# KLogShield_Interface_Rev1.net
KiCad netlist of a schematic drawn in Altium Designer
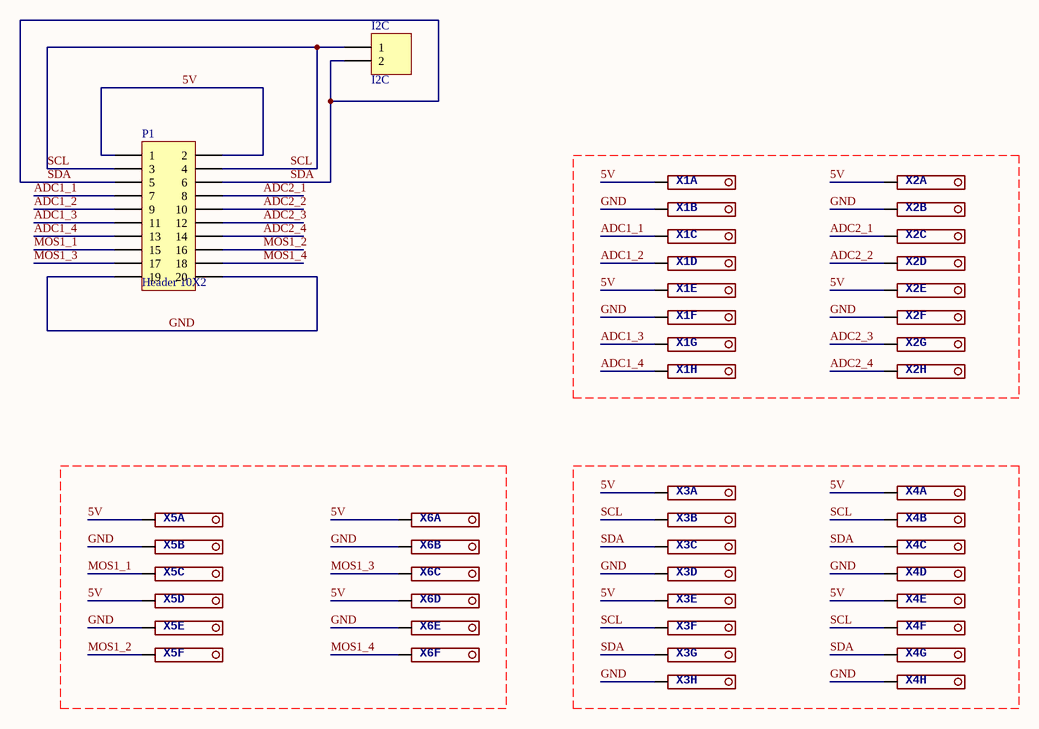
[diagram p0: KLogShield_Interface_Rev1.SchDoc]

(export (version "E")
  (design (tool "Eeschema 10.0.6"))
  (components
    (comp (ref "I2C")
      (value "I2C")
      (footprint "HDR1X2")
      (description "Header, 2-Pin")
      (fields (field (name "PUBLISHER") "Altium Limited"))
      (libsource (lib "Miscellaneous Connectors") (part "Header 2"))
    )
    (comp (ref "P1")
      (value "Header 10X2")
      (footprint "HDR2X10")
      (description "Header, 10-Pin, Dual row")
      (fields (field (name "PUBLISHER") "Altium Limited"))
      (libsource (lib "Miscellaneous Connectors") (part "Header 10X2"))
    )
    (comp (ref "X1") (value "~") (footprint "1751303") (libsource (lib "con-phoenix-350") (part "1751303")))
    (comp (ref "X2") (value "~") (footprint "1751303") (libsource (lib "con-phoenix-350") (part "1751303")))
    (comp (ref "X3") (value "~") (footprint "1751303") (libsource (lib "con-phoenix-350") (part "1751303")))
    (comp (ref "X4") (value "~") (footprint "1751303") (libsource (lib "con-phoenix-350") (part "1751303")))
    (comp (ref "X5")
      (value "~")
      (footprint "1751280")
      (fields (field (name "MPN") "1751280"))
      (libsource (lib "con-phoenix-350") (part "1751280"))
    )
    (comp (ref "X6")
      (value "~")
      (footprint "1751280")
      (fields (field (name "MPN") "1751280"))
      (libsource (lib "con-phoenix-350") (part "1751280"))
    )
  )
  (nets
    (net (code "1") (name "/5V") (class "Default")
      (node (ref "P1") (pin "1") (pinfunction "1_1") (pintype "passive"))
      (node (ref "P1") (pin "2") (pinfunction "2_2") (pintype "passive"))
      (node (ref "X1") (pin "1") (pinfunction "K_1") (pintype "passive"))
      (node (ref "X1") (pin "5") (pinfunction "K_5") (pintype "passive"))
      (node (ref "X2") (pin "1") (pinfunction "K_1") (pintype "passive"))
      (node (ref "X2") (pin "5") (pinfunction "K_5") (pintype "passive"))
      (node (ref "X3") (pin "1") (pinfunction "K_1") (pintype "passive"))
      (node (ref "X3") (pin "5") (pinfunction "K_5") (pintype "passive"))
      (node (ref "X4") (pin "1") (pinfunction "K_1") (pintype "passive"))
      (node (ref "X4") (pin "5") (pinfunction "K_5") (pintype "passive"))
      (node (ref "X5") (pin "1") (pinfunction "K_1") (pintype "passive"))
      (node (ref "X5") (pin "4") (pinfunction "K_4") (pintype "passive"))
      (node (ref "X6") (pin "1") (pinfunction "K_1") (pintype "passive"))
      (node (ref "X6") (pin "4") (pinfunction "K_4") (pintype "passive"))
    )
    (net (code "2") (name "/ADC1_1") (class "Default")
      (node (ref "P1") (pin "7") (pinfunction "7_7") (pintype "passive"))
      (node (ref "X1") (pin "3") (pinfunction "K_3") (pintype "passive"))
    )
    (net (code "3") (name "/ADC1_2") (class "Default")
      (node (ref "P1") (pin "9") (pinfunction "9_9") (pintype "passive"))
      (node (ref "X1") (pin "4") (pinfunction "K_4") (pintype "passive"))
    )
    (net (code "4") (name "/ADC1_3") (class "Default")
      (node (ref "P1") (pin "11") (pinfunction "11_11") (pintype "passive"))
      (node (ref "X1") (pin "7") (pinfunction "K_7") (pintype "passive"))
    )
    (net (code "5") (name "/ADC1_4") (class "Default")
      (node (ref "P1") (pin "13") (pinfunction "13_13") (pintype "passive"))
      (node (ref "X1") (pin "8") (pinfunction "K_8") (pintype "passive"))
    )
    (net (code "6") (name "/ADC2_1") (class "Default")
      (node (ref "P1") (pin "8") (pinfunction "8_8") (pintype "passive"))
      (node (ref "X2") (pin "3") (pinfunction "K_3") (pintype "passive"))
    )
    (net (code "7") (name "/ADC2_2") (class "Default")
      (node (ref "P1") (pin "10") (pinfunction "10_10") (pintype "passive"))
      (node (ref "X2") (pin "4") (pinfunction "K_4") (pintype "passive"))
    )
    (net (code "8") (name "/ADC2_3") (class "Default")
      (node (ref "P1") (pin "12") (pinfunction "12_12") (pintype "passive"))
      (node (ref "X2") (pin "7") (pinfunction "K_7") (pintype "passive"))
    )
    (net (code "9") (name "/ADC2_4") (class "Default")
      (node (ref "P1") (pin "14") (pinfunction "14_14") (pintype "passive"))
      (node (ref "X2") (pin "8") (pinfunction "K_8") (pintype "passive"))
    )
    (net (code "10") (name "/GND") (class "Default")
      (node (ref "P1") (pin "19") (pinfunction "19_19") (pintype "passive"))
      (node (ref "P1") (pin "20") (pinfunction "20_20") (pintype "passive"))
      (node (ref "X1") (pin "2") (pinfunction "K_2") (pintype "passive"))
      (node (ref "X1") (pin "6") (pinfunction "K_6") (pintype "passive"))
      (node (ref "X2") (pin "2") (pinfunction "K_2") (pintype "passive"))
      (node (ref "X2") (pin "6") (pinfunction "K_6") (pintype "passive"))
      (node (ref "X3") (pin "4") (pinfunction "K_4") (pintype "passive"))
      (node (ref "X3") (pin "8") (pinfunction "K_8") (pintype "passive"))
      (node (ref "X4") (pin "4") (pinfunction "K_4") (pintype "passive"))
      (node (ref "X4") (pin "8") (pinfunction "K_8") (pintype "passive"))
      (node (ref "X5") (pin "2") (pinfunction "K_2") (pintype "passive"))
      (node (ref "X5") (pin "5") (pinfunction "K_5") (pintype "passive"))
      (node (ref "X6") (pin "2") (pinfunction "K_2") (pintype "passive"))
      (node (ref "X6") (pin "5") (pinfunction "K_5") (pintype "passive"))
    )
    (net (code "11") (name "/MOS1_1") (class "Default")
      (node (ref "P1") (pin "15") (pinfunction "15_15") (pintype "passive"))
      (node (ref "X5") (pin "3") (pinfunction "K_3") (pintype "passive"))
    )
    (net (code "12") (name "/MOS1_2") (class "Default")
      (node (ref "P1") (pin "16") (pinfunction "16_16") (pintype "passive"))
      (node (ref "X5") (pin "6") (pinfunction "K_6") (pintype "passive"))
    )
    (net (code "13") (name "/MOS1_3") (class "Default")
      (node (ref "P1") (pin "17") (pinfunction "17_17") (pintype "passive"))
      (node (ref "X6") (pin "3") (pinfunction "K_3") (pintype "passive"))
    )
    (net (code "14") (name "/MOS1_4") (class "Default")
      (node (ref "P1") (pin "18") (pinfunction "18_18") (pintype "passive"))
      (node (ref "X6") (pin "6") (pinfunction "K_6") (pintype "passive"))
    )
    (net (code "15") (name "/SCL") (class "Default")
      (node (ref "I2C") (pin "1") (pinfunction "1_1") (pintype "passive"))
      (node (ref "P1") (pin "3") (pinfunction "3_3") (pintype "passive"))
      (node (ref "P1") (pin "4") (pinfunction "4_4") (pintype "passive"))
      (node (ref "X3") (pin "2") (pinfunction "K_2") (pintype "passive"))
      (node (ref "X3") (pin "6") (pinfunction "K_6") (pintype "passive"))
      (node (ref "X4") (pin "2") (pinfunction "K_2") (pintype "passive"))
      (node (ref "X4") (pin "6") (pinfunction "K_6") (pintype "passive"))
    )
    (net (code "16") (name "/SDA") (class "Default")
      (node (ref "I2C") (pin "2") (pinfunction "2_2") (pintype "passive"))
      (node (ref "P1") (pin "5") (pinfunction "5_5") (pintype "passive"))
      (node (ref "P1") (pin "6") (pinfunction "6_6") (pintype "passive"))
      (node (ref "X3") (pin "3") (pinfunction "K_3") (pintype "passive"))
      (node (ref "X3") (pin "7") (pinfunction "K_7") (pintype "passive"))
      (node (ref "X4") (pin "3") (pinfunction "K_3") (pintype "passive"))
      (node (ref "X4") (pin "7") (pinfunction "K_7") (pintype "passive"))
    )
  )
)
